# tides_v40.net
KiCad netlist of a schematic drawn in EAGLE
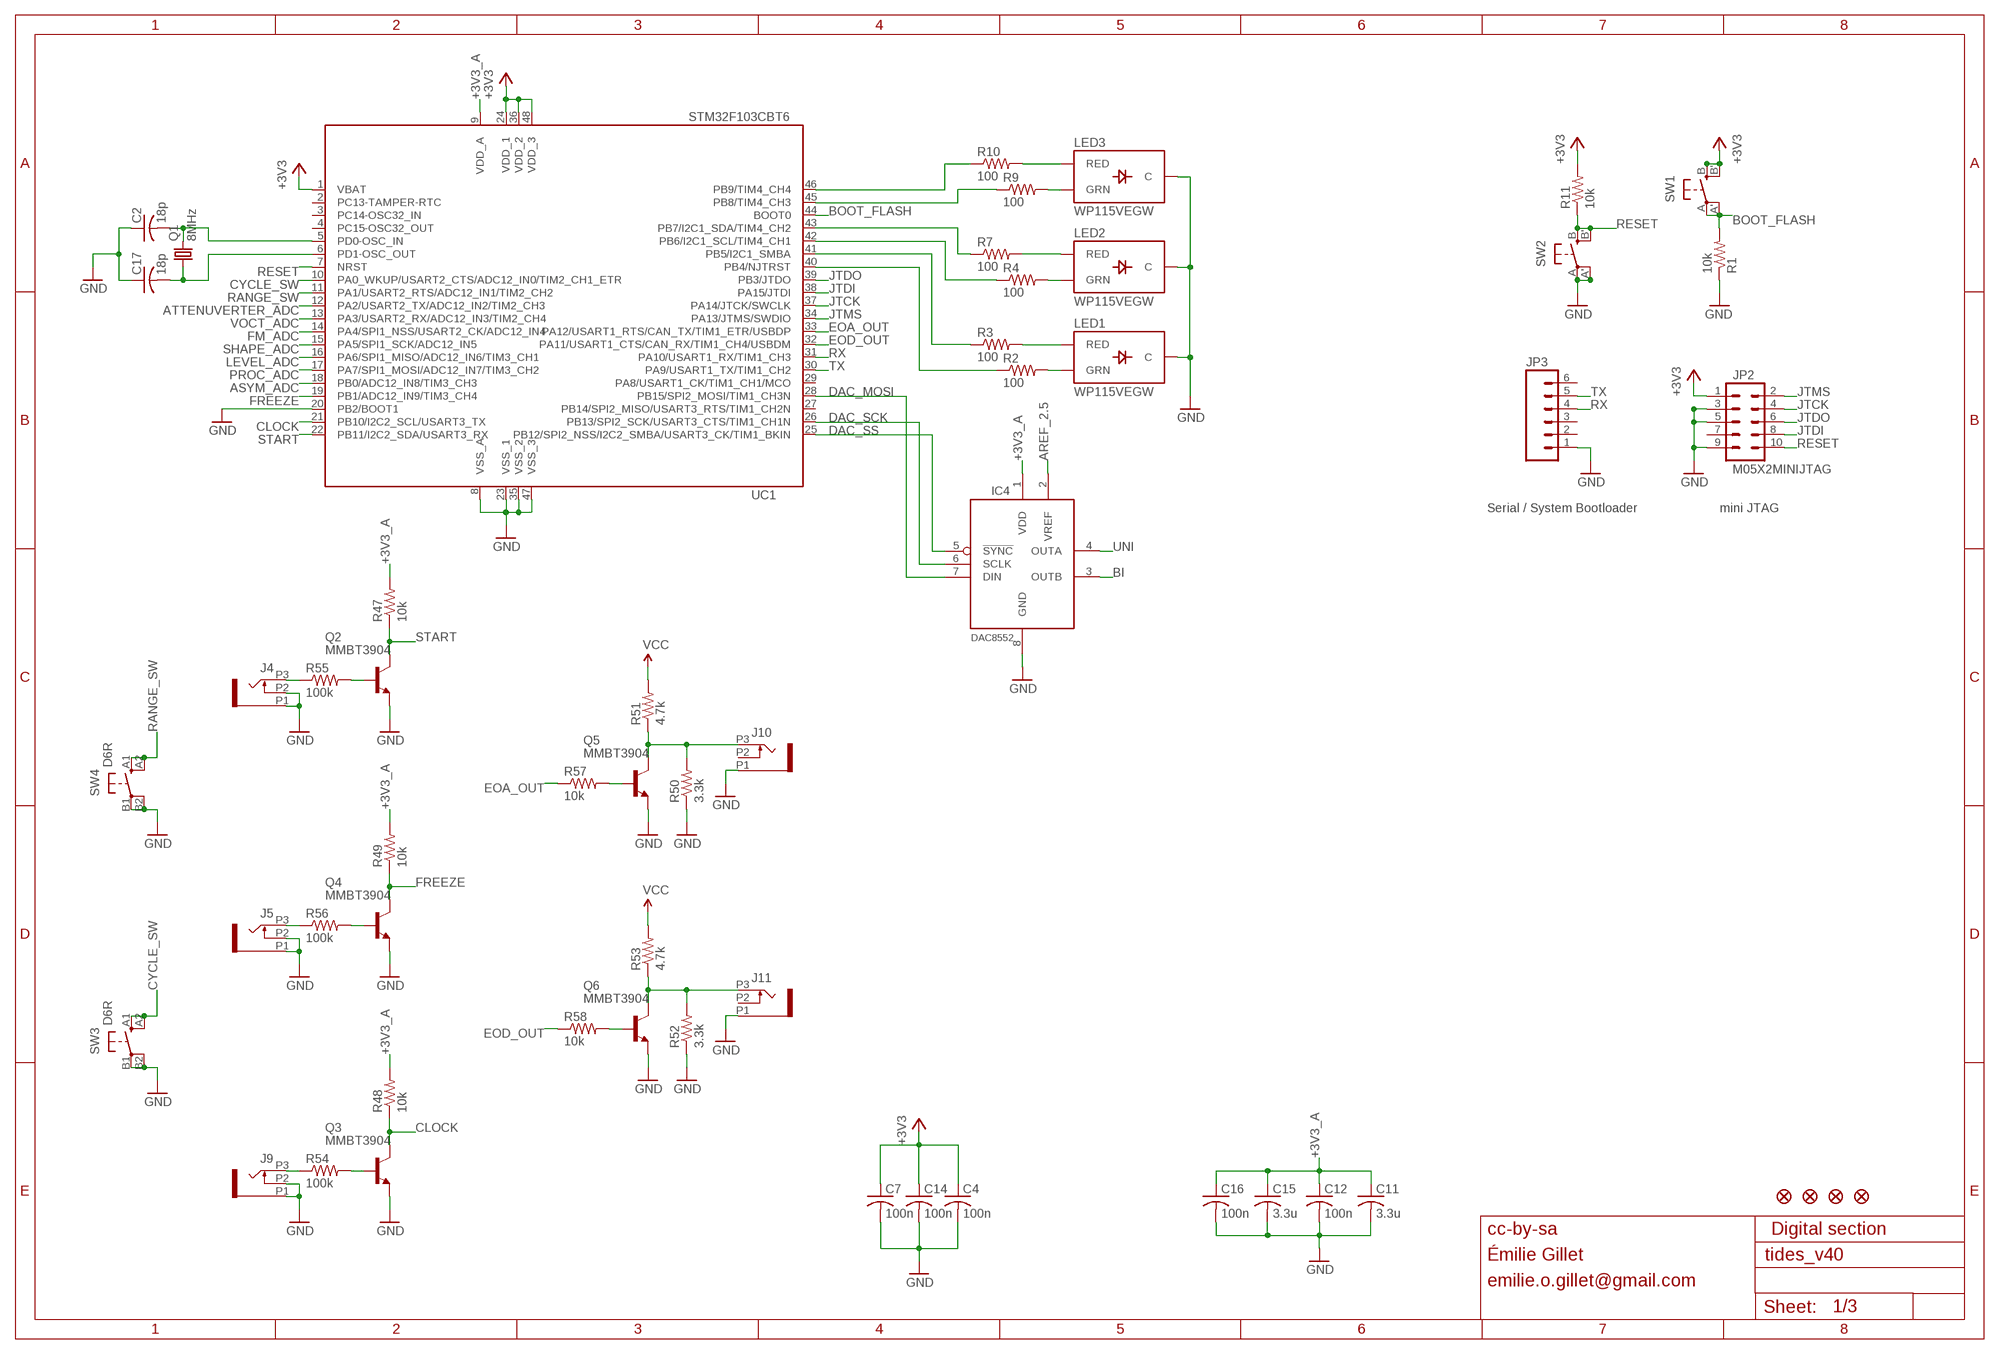
[diagram p0: schematic, sheet 1]
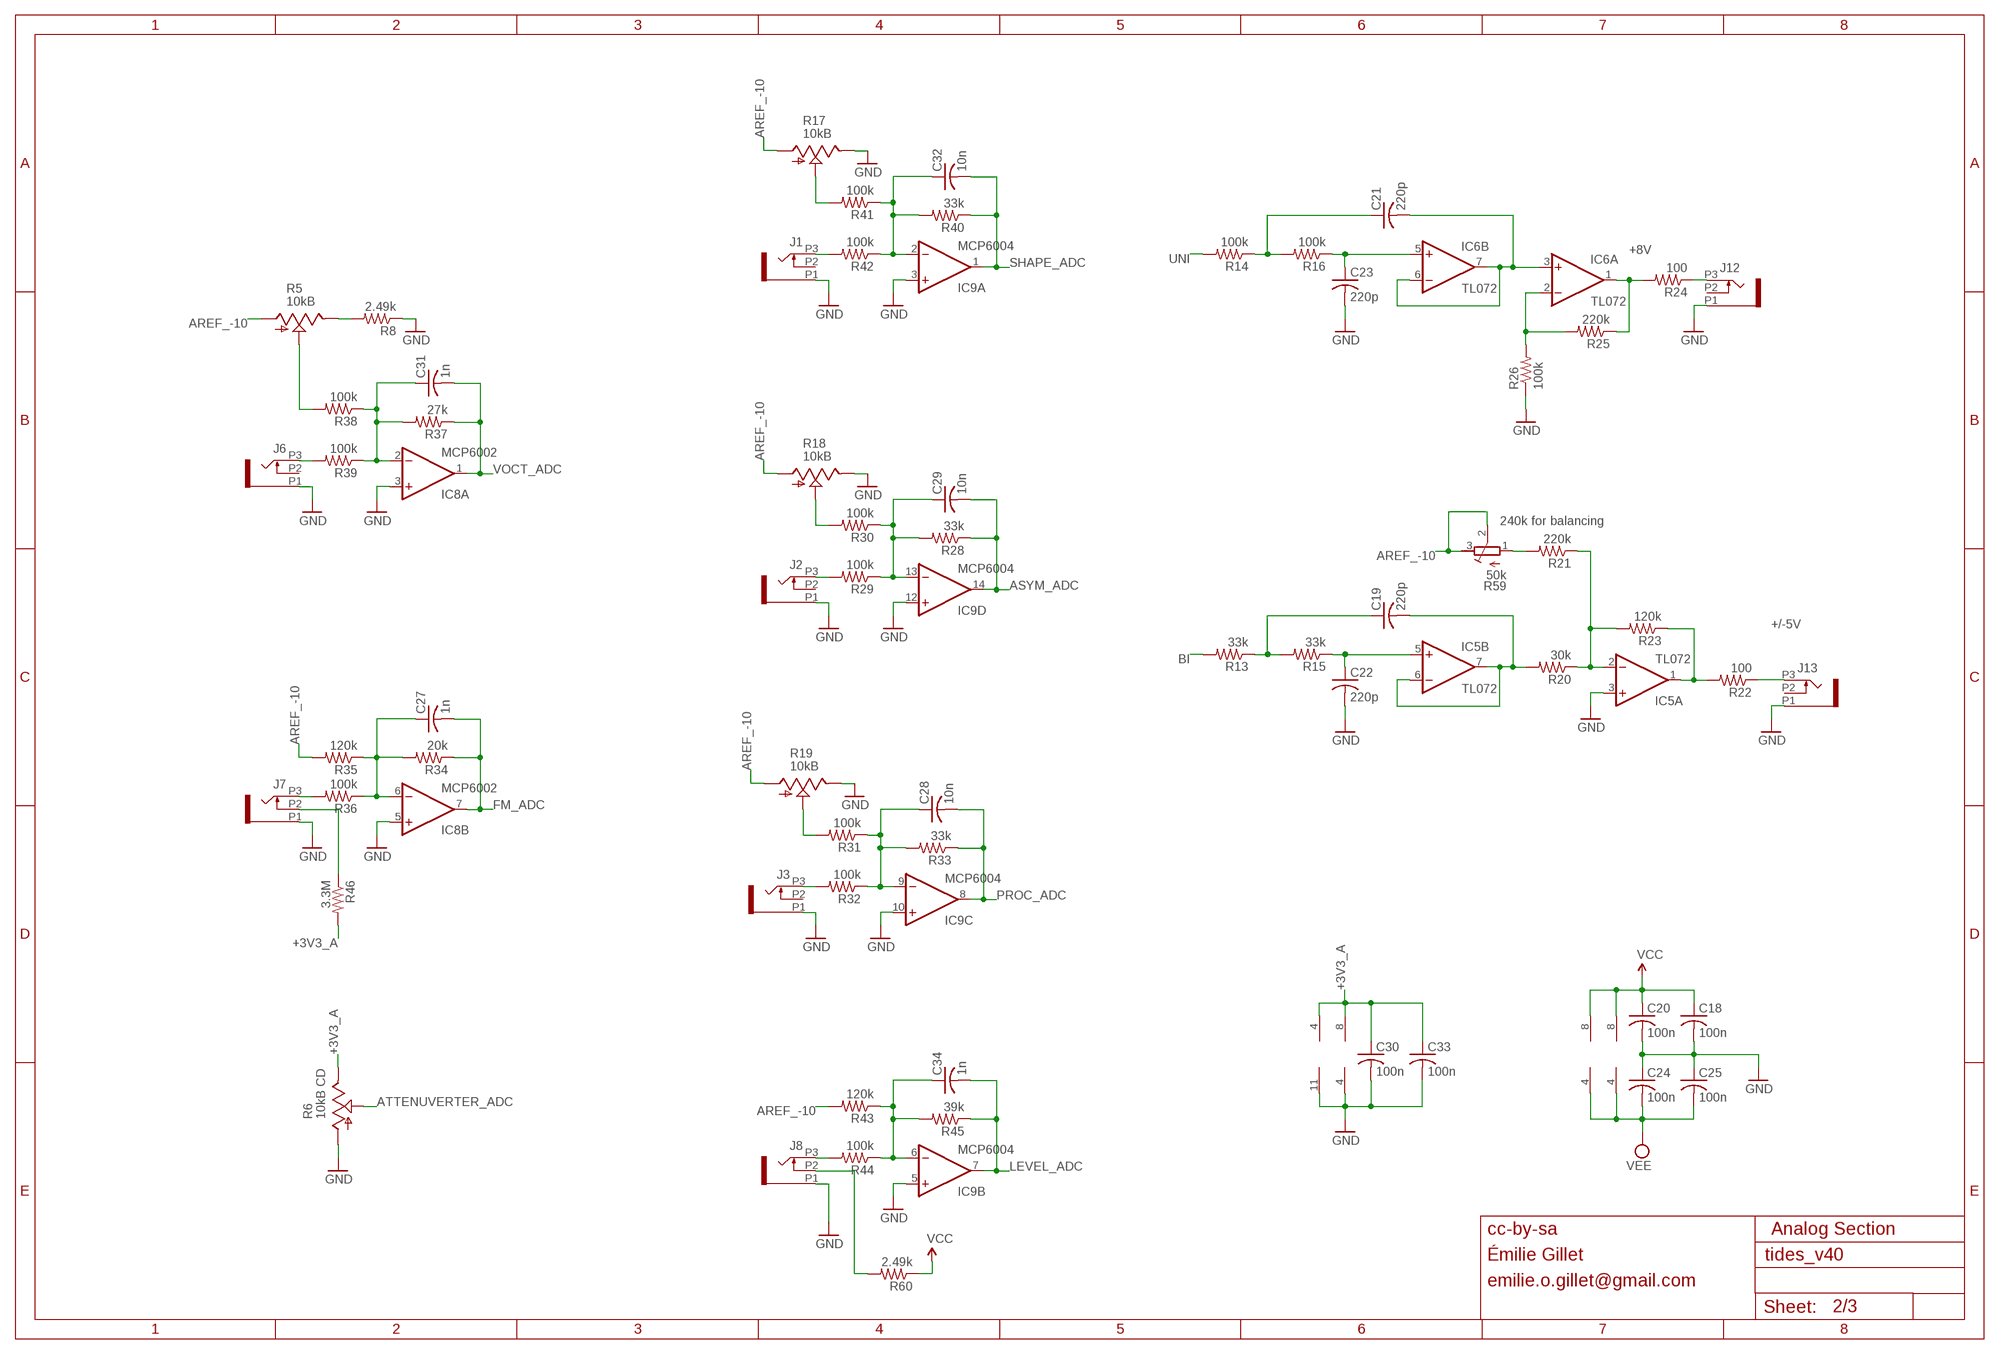
[diagram p1: schematic, sheet 2]
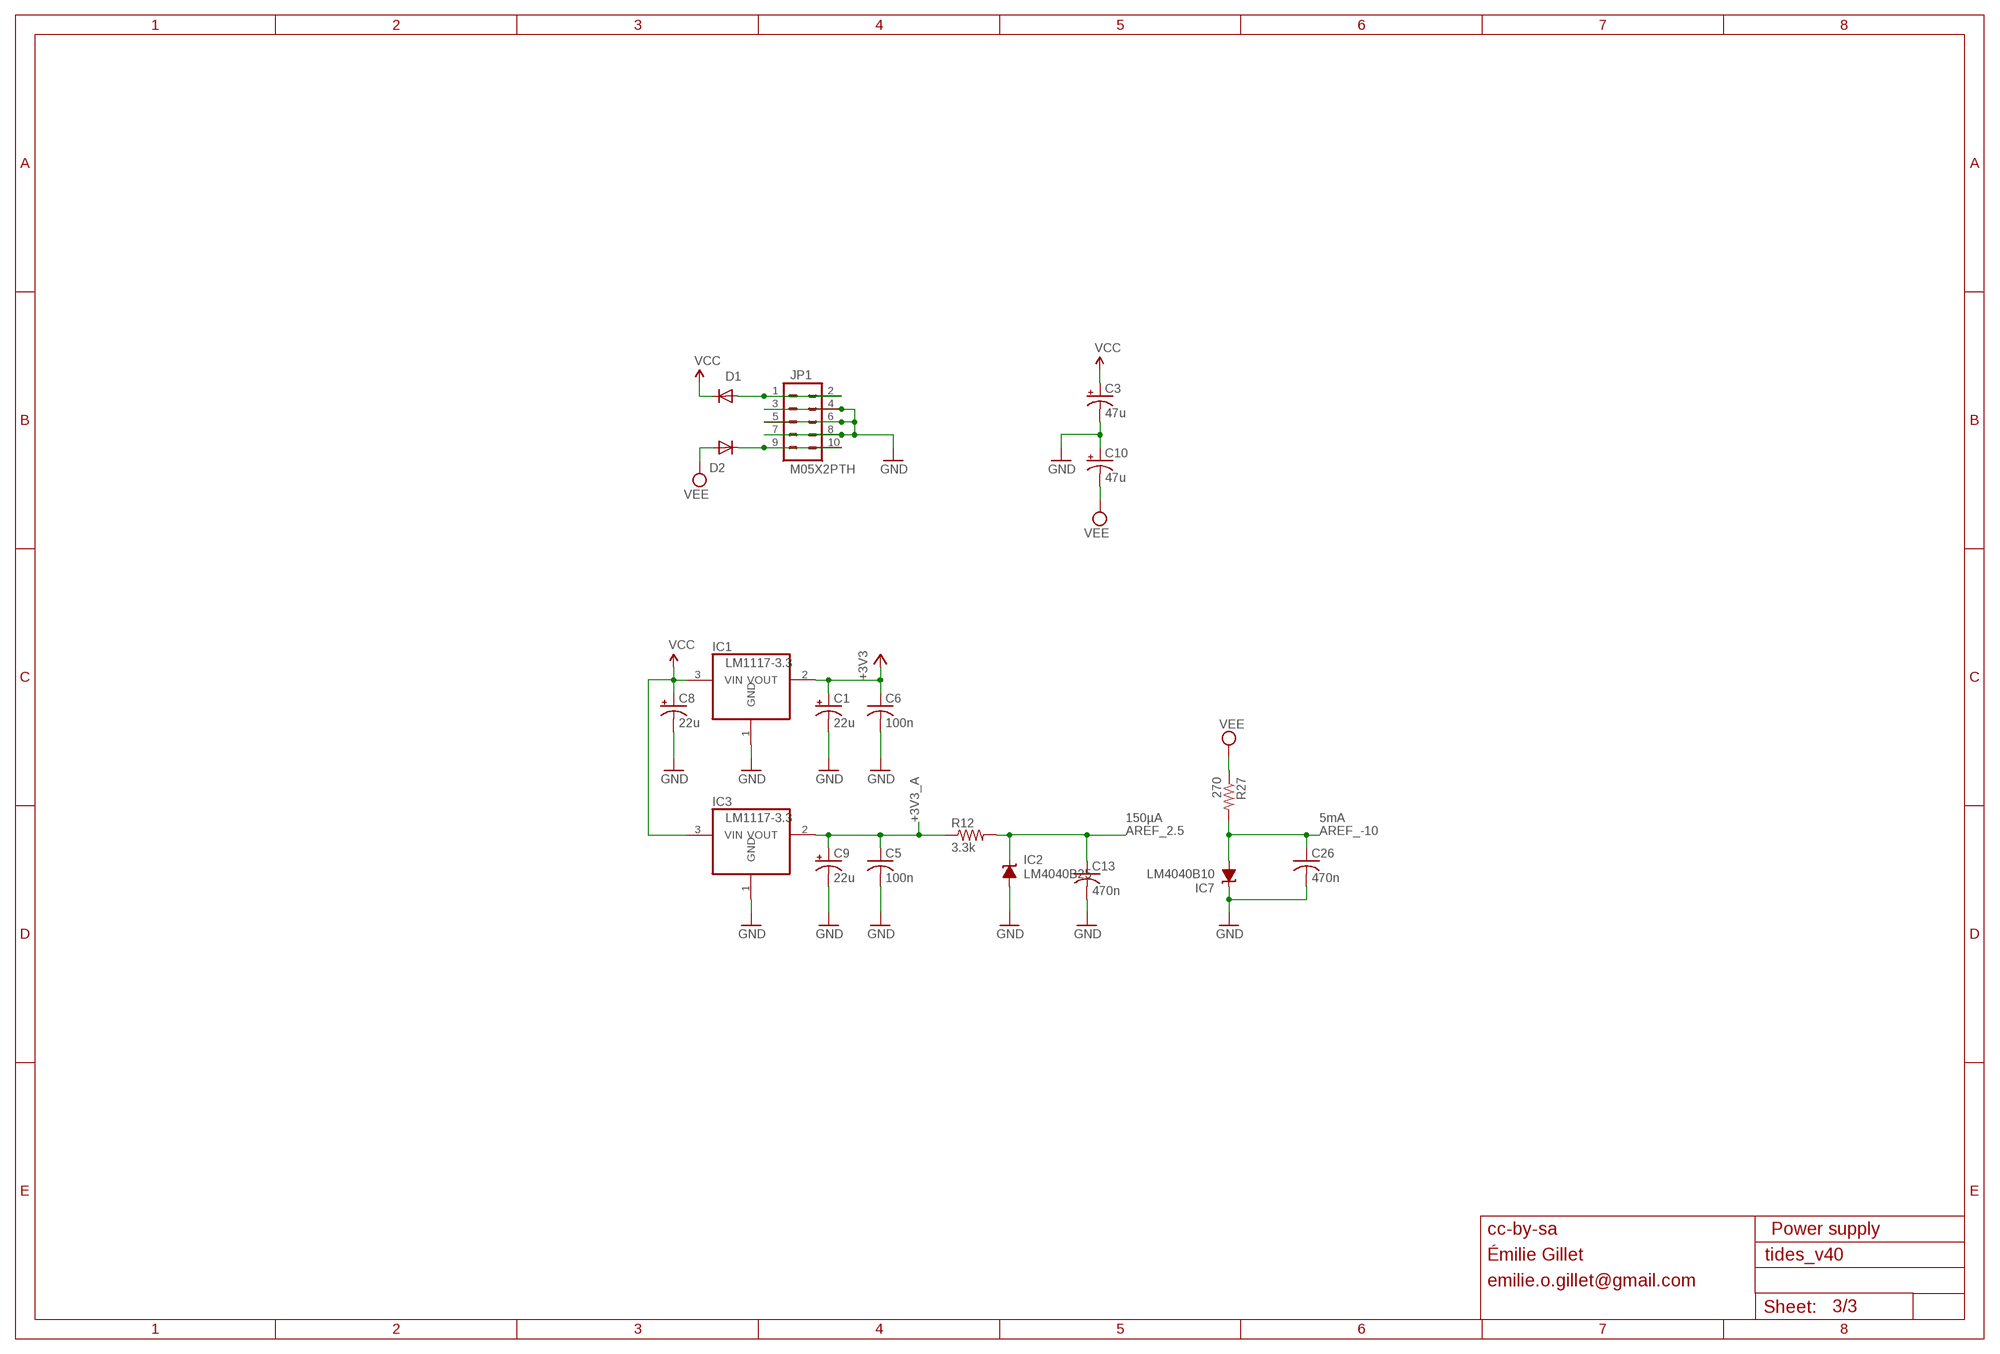
[diagram p2: schematic, sheet 3]

(export (version "E")
  (design (tool "Eeschema 10.0.6"))
  (components
    (comp (ref "C2")
      (value "18p")
      (footprint "eagle-import:C0603")
      (libsource (lib "eagle-import") (part "C-USC0603"))
    )
    (comp (ref "C4")
      (value "100n")
      (footprint "eagle-import:C0603")
      (libsource (lib "eagle-import") (part "C-USC0603"))
    )
    (comp (ref "C7")
      (value "100n")
      (footprint "eagle-import:C0603")
      (libsource (lib "eagle-import") (part "C-USC0603"))
    )
    (comp (ref "C11")
      (value "3.3u")
      (footprint "eagle-import:C0603")
      (libsource (lib "eagle-import") (part "C-USC0603"))
    )
    (comp (ref "C12")
      (value "100n")
      (footprint "eagle-import:C0603")
      (libsource (lib "eagle-import") (part "C-USC0603"))
    )
    (comp (ref "C14")
      (value "100n")
      (footprint "eagle-import:C0603")
      (libsource (lib "eagle-import") (part "C-USC0603"))
    )
    (comp (ref "C15")
      (value "3.3u")
      (footprint "eagle-import:C0603")
      (libsource (lib "eagle-import") (part "C-USC0603"))
    )
    (comp (ref "C16")
      (value "100n")
      (footprint "eagle-import:C0603")
      (libsource (lib "eagle-import") (part "C-USC0603"))
    )
    (comp (ref "C17")
      (value "18p")
      (footprint "eagle-import:C0603")
      (libsource (lib "eagle-import") (part "C-USC0603"))
    )
    (comp (ref "IC4")
      (value "DAC8552")
      (footprint "eagle-import:MSOP-8")
      (libsource (lib "eagle-import") (part "DAC8552"))
    )
    (comp (ref "J4")
      (value "PJ301_THONKICONN6")
      (footprint "eagle-import:WQP_PJ_301M6")
      (libsource (lib "eagle-import") (part "PJ301_THONKICONN6"))
    )
    (comp (ref "J5")
      (value "PJ301_THONKICONN6")
      (footprint "eagle-import:WQP_PJ_301M6")
      (libsource (lib "eagle-import") (part "PJ301_THONKICONN6"))
    )
    (comp (ref "J9")
      (value "PJ301_THONKICONN6")
      (footprint "eagle-import:WQP_PJ_301M6")
      (libsource (lib "eagle-import") (part "PJ301_THONKICONN6"))
    )
    (comp (ref "J10")
      (value "PJ301_THONKICONN6")
      (footprint "eagle-import:WQP_PJ_301M6")
      (libsource (lib "eagle-import") (part "PJ301_THONKICONN6"))
    )
    (comp (ref "J11")
      (value "PJ301_THONKICONN6")
      (footprint "eagle-import:WQP_PJ_301M6")
      (libsource (lib "eagle-import") (part "PJ301_THONKICONN6"))
    )
    (comp (ref "JP2")
      (value "M05X2MINIJTAG")
      (footprint "eagle-import:2X5-1.27")
      (libsource (lib "eagle-import") (part "M05X2MINIJTAG"))
    )
    (comp (ref "JP3")
      (value "M06SIP")
      (footprint "eagle-import:1X06")
      (libsource (lib "eagle-import") (part "M06SIP"))
    )
    (comp (ref "JP4")
      (value "FIDUCIAL1X2")
      (footprint "eagle-import:FIDUCIAL-1X2")
      (libsource (lib "eagle-import") (part "FIDUCIAL1X2"))
    )
    (comp (ref "JP5")
      (value "FIDUCIAL1X2")
      (footprint "eagle-import:FIDUCIAL-1X2")
      (libsource (lib "eagle-import") (part "FIDUCIAL1X2"))
    )
    (comp (ref "JP6")
      (value "FIDUCIAL1X2")
      (footprint "eagle-import:FIDUCIAL-1X2")
      (libsource (lib "eagle-import") (part "FIDUCIAL1X2"))
    )
    (comp (ref "JP7")
      (value "FIDUCIAL1X2")
      (footprint "eagle-import:FIDUCIAL-1X2")
      (libsource (lib "eagle-import") (part "FIDUCIAL1X2"))
    )
    (comp (ref "LED1")
      (value "WP115VEGW")
      (footprint "eagle-import:LED-BICOLOR-THROUGHHOLE")
      (libsource (lib "eagle-import") (part "LED-BICOLOR-THROUGHHOLE"))
    )
    (comp (ref "LED2")
      (value "WP115VEGW")
      (footprint "eagle-import:LED-BICOLOR-THROUGHHOLE")
      (libsource (lib "eagle-import") (part "LED-BICOLOR-THROUGHHOLE"))
    )
    (comp (ref "LED3")
      (value "WP115VEGW")
      (footprint "eagle-import:LED-BICOLOR-THROUGHHOLE")
      (libsource (lib "eagle-import") (part "LED-BICOLOR-THROUGHHOLE"))
    )
    (comp (ref "Q1")
      (value "8MHz")
      (footprint "eagle-import:HC49UP")
      (libsource (lib "eagle-import") (part "CRYSTALHC49UP"))
    )
    (comp (ref "Q2")
      (value "MMBT3904")
      (footprint "eagle-import:SOT23-BEC")
      (libsource (lib "eagle-import") (part "-NPN-SOT23-BECMMBT3904LT1"))
    )
    (comp (ref "Q3")
      (value "MMBT3904")
      (footprint "eagle-import:SOT23-BEC")
      (libsource (lib "eagle-import") (part "-NPN-SOT23-BECMMBT3904LT1"))
    )
    (comp (ref "Q4")
      (value "MMBT3904")
      (footprint "eagle-import:SOT23-BEC")
      (libsource (lib "eagle-import") (part "-NPN-SOT23-BECMMBT3904LT1"))
    )
    (comp (ref "Q5")
      (value "MMBT3904")
      (footprint "eagle-import:SOT23-BEC")
      (libsource (lib "eagle-import") (part "-NPN-SOT23-BECMMBT3904LT1"))
    )
    (comp (ref "Q6")
      (value "MMBT3904")
      (footprint "eagle-import:SOT23-BEC")
      (libsource (lib "eagle-import") (part "-NPN-SOT23-BECMMBT3904LT1"))
    )
    (comp (ref "R1")
      (value "10k")
      (footprint "eagle-import:R0603")
      (libsource (lib "eagle-import") (part "R-US_R0603"))
    )
    (comp (ref "R2")
      (value "100")
      (footprint "eagle-import:R0603")
      (libsource (lib "eagle-import") (part "R-US_R0603"))
    )
    (comp (ref "R3")
      (value "100")
      (footprint "eagle-import:R0603")
      (libsource (lib "eagle-import") (part "R-US_R0603"))
    )
    (comp (ref "R4")
      (value "100")
      (footprint "eagle-import:R0603")
      (libsource (lib "eagle-import") (part "R-US_R0603"))
    )
    (comp (ref "R7")
      (value "100")
      (footprint "eagle-import:R0603")
      (libsource (lib "eagle-import") (part "R-US_R0603"))
    )
    (comp (ref "R9")
      (value "100")
      (footprint "eagle-import:R0603")
      (libsource (lib "eagle-import") (part "R-US_R0603"))
    )
    (comp (ref "R10")
      (value "100")
      (footprint "eagle-import:R0603")
      (libsource (lib "eagle-import") (part "R-US_R0603"))
    )
    (comp (ref "R11")
      (value "10k")
      (footprint "eagle-import:R0603")
      (libsource (lib "eagle-import") (part "R-US_R0603"))
    )
    (comp (ref "R47")
      (value "10k")
      (footprint "eagle-import:R0603")
      (libsource (lib "eagle-import") (part "R-US_R0603"))
    )
    (comp (ref "R48")
      (value "10k")
      (footprint "eagle-import:R0603")
      (libsource (lib "eagle-import") (part "R-US_R0603"))
    )
    (comp (ref "R49")
      (value "10k")
      (footprint "eagle-import:R0603")
      (libsource (lib "eagle-import") (part "R-US_R0603"))
    )
    (comp (ref "R50")
      (value "3.3k")
      (footprint "eagle-import:R0603")
      (libsource (lib "eagle-import") (part "R-US_R0603"))
    )
    (comp (ref "R51")
      (value "4.7k")
      (footprint "eagle-import:R0603")
      (libsource (lib "eagle-import") (part "R-US_R0603"))
    )
    (comp (ref "R52")
      (value "3.3k")
      (footprint "eagle-import:R0603")
      (libsource (lib "eagle-import") (part "R-US_R0603"))
    )
    (comp (ref "R53")
      (value "4.7k")
      (footprint "eagle-import:R0603")
      (libsource (lib "eagle-import") (part "R-US_R0603"))
    )
    (comp (ref "R54")
      (value "100k")
      (footprint "eagle-import:R0603")
      (libsource (lib "eagle-import") (part "R-US_R0603"))
    )
    (comp (ref "R55")
      (value "100k")
      (footprint "eagle-import:R0603")
      (libsource (lib "eagle-import") (part "R-US_R0603"))
    )
    (comp (ref "R56")
      (value "100k")
      (footprint "eagle-import:R0603")
      (libsource (lib "eagle-import") (part "R-US_R0603"))
    )
    (comp (ref "R57")
      (value "10k")
      (footprint "eagle-import:R0603")
      (libsource (lib "eagle-import") (part "R-US_R0603"))
    )
    (comp (ref "R58")
      (value "10k")
      (footprint "eagle-import:R0603")
      (libsource (lib "eagle-import") (part "R-US_R0603"))
    )
    (comp (ref "SW1")
      (value "EVQQ2")
      (footprint "eagle-import:EVQ-Q2")
      (libsource (lib "eagle-import") (part "EVQQ2"))
    )
    (comp (ref "SW2")
      (value "EVQQ2")
      (footprint "eagle-import:EVQ-Q2")
      (libsource (lib "eagle-import") (part "EVQQ2"))
    )
    (comp (ref "SW3")
      (value "D6R")
      (footprint "eagle-import:D6R")
      (libsource (lib "eagle-import") (part "D6R"))
    )
    (comp (ref "SW4")
      (value "D6R")
      (footprint "eagle-import:D6R")
      (libsource (lib "eagle-import") (part "D6R"))
    )
    (comp (ref "UC1")
      (value "STM32F103CBT6")
      (footprint "eagle-import:LQFP48")
      (libsource (lib "eagle-import") (part "STM32F103CB"))
    )
    (comp (ref "C1")
      (value "22u")
      (footprint "eagle-import:PANASONIC_C")
      (libsource (lib "eagle-import") (part "CPOL-USC"))
    )
    (comp (ref "C3")
      (value "47u")
      (footprint "eagle-import:PANASONIC_D")
      (libsource (lib "eagle-import") (part "CPOL-USD"))
    )
    (comp (ref "C5")
      (value "100n")
      (footprint "eagle-import:C0603")
      (libsource (lib "eagle-import") (part "C-USC0603"))
    )
    (comp (ref "C6")
      (value "100n")
      (footprint "eagle-import:C0603")
      (libsource (lib "eagle-import") (part "C-USC0603"))
    )
    (comp (ref "C8")
      (value "22u")
      (footprint "eagle-import:PANASONIC_C")
      (libsource (lib "eagle-import") (part "CPOL-USC"))
    )
    (comp (ref "C9")
      (value "22u")
      (footprint "eagle-import:PANASONIC_C")
      (libsource (lib "eagle-import") (part "CPOL-USC"))
    )
    (comp (ref "C10")
      (value "47u")
      (footprint "eagle-import:PANASONIC_D")
      (libsource (lib "eagle-import") (part "CPOL-USD"))
    )
    (comp (ref "C13")
      (value "470n")
      (footprint "eagle-import:C0603")
      (libsource (lib "eagle-import") (part "C-USC0603"))
    )
    (comp (ref "C26")
      (value "470n")
      (footprint "eagle-import:C0603")
      (libsource (lib "eagle-import") (part "C-USC0603"))
    )
    (comp (ref "D1")
      (value "1N5819HW")
      (footprint "eagle-import:SOD123")
      (libsource (lib "eagle-import") (part "DIODE-SOD123"))
    )
    (comp (ref "D2")
      (value "1N5819HW")
      (footprint "eagle-import:SOD123")
      (libsource (lib "eagle-import") (part "DIODE-SOD123"))
    )
    (comp (ref "IC1")
      (value "LM1117-3.3")
      (footprint "eagle-import:SOT223")
      (libsource (lib "eagle-import") (part "REG1117"))
    )
    (comp (ref "IC2")
      (value "LM4040B25")
      (footprint "eagle-import:DBZ_R-PDSO-G3")
      (libsource (lib "eagle-import") (part "LM4041DBZB12"))
    )
    (comp (ref "IC3")
      (value "LM1117-3.3")
      (footprint "eagle-import:SOT223")
      (libsource (lib "eagle-import") (part "REG1117"))
    )
    (comp (ref "IC7")
      (value "LM4040B10")
      (footprint "eagle-import:DBZ_R-PDSO-G3")
      (libsource (lib "eagle-import") (part "LM4041DBZB12"))
    )
    (comp (ref "JP1")
      (value "M05X2PTH")
      (footprint "eagle-import:AVR_ICSP")
      (libsource (lib "eagle-import") (part "M05X2PTH"))
    )
    (comp (ref "R12")
      (value "3.3k")
      (footprint "eagle-import:R0603")
      (libsource (lib "eagle-import") (part "R-US_R0603"))
    )
    (comp (ref "R27")
      (value "270")
      (footprint "eagle-import:R0603")
      (libsource (lib "eagle-import") (part "R-US_R0603"))
    )
    (comp (ref "C18")
      (value "100n")
      (footprint "eagle-import:C0603")
      (libsource (lib "eagle-import") (part "C-USC0603"))
    )
    (comp (ref "C19")
      (value "220p")
      (footprint "eagle-import:C0603")
      (libsource (lib "eagle-import") (part "C-USC0603"))
    )
    (comp (ref "C20")
      (value "100n")
      (footprint "eagle-import:C0603")
      (libsource (lib "eagle-import") (part "C-USC0603"))
    )
    (comp (ref "C21")
      (value "220p")
      (footprint "eagle-import:C0603")
      (libsource (lib "eagle-import") (part "C-USC0603"))
    )
    (comp (ref "C22")
      (value "220p")
      (footprint "eagle-import:C0603")
      (libsource (lib "eagle-import") (part "C-USC0603"))
    )
    (comp (ref "C23")
      (value "220p")
      (footprint "eagle-import:C0603")
      (libsource (lib "eagle-import") (part "C-USC0603"))
    )
    (comp (ref "C24")
      (value "100n")
      (footprint "eagle-import:C0603")
      (libsource (lib "eagle-import") (part "C-USC0603"))
    )
    (comp (ref "C25")
      (value "100n")
      (footprint "eagle-import:C0603")
      (libsource (lib "eagle-import") (part "C-USC0603"))
    )
    (comp (ref "C27")
      (value "1n")
      (footprint "eagle-import:C0603")
      (libsource (lib "eagle-import") (part "C-USC0603"))
    )
    (comp (ref "C28")
      (value "10n")
      (footprint "eagle-import:C0603")
      (libsource (lib "eagle-import") (part "C-USC0603"))
    )
    (comp (ref "C29")
      (value "10n")
      (footprint "eagle-import:C0603")
      (libsource (lib "eagle-import") (part "C-USC0603"))
    )
    (comp (ref "C30")
      (value "100n")
      (footprint "eagle-import:C0603")
      (libsource (lib "eagle-import") (part "C-USC0603"))
    )
    (comp (ref "C31")
      (value "1n")
      (footprint "eagle-import:C0603")
      (libsource (lib "eagle-import") (part "C-USC0603"))
    )
    (comp (ref "C32")
      (value "10n")
      (footprint "eagle-import:C0603")
      (libsource (lib "eagle-import") (part "C-USC0603"))
    )
    (comp (ref "C33")
      (value "100n")
      (footprint "eagle-import:C0603")
      (libsource (lib "eagle-import") (part "C-USC0603"))
    )
    (comp (ref "C34")
      (value "1n")
      (footprint "eagle-import:C0603")
      (libsource (lib "eagle-import") (part "C-USC0603"))
    )
    (comp (ref "IC5")
      (value "TL072")
      (footprint "eagle-import:SO08")
      (libsource (lib "eagle-import") (part "TL072D"))
    )
    (comp (ref "IC6")
      (value "TL072")
      (footprint "eagle-import:SO08")
      (libsource (lib "eagle-import") (part "TL072D"))
    )
    (comp (ref "IC8")
      (value "MCP6002")
      (footprint "eagle-import:SO08")
      (libsource (lib "eagle-import") (part "TL072D"))
    )
    (comp (ref "IC9")
      (value "MCP6004")
      (footprint "eagle-import:SO14")
      (libsource (lib "eagle-import") (part "TL074D"))
    )
    (comp (ref "J1")
      (value "PJ301_THONKICONN6")
      (footprint "eagle-import:WQP_PJ_301M6")
      (libsource (lib "eagle-import") (part "PJ301_THONKICONN6"))
    )
    (comp (ref "J2")
      (value "PJ301_THONKICONN6")
      (footprint "eagle-import:WQP_PJ_301M6")
      (libsource (lib "eagle-import") (part "PJ301_THONKICONN6"))
    )
    (comp (ref "J3")
      (value "PJ301_THONKICONN6")
      (footprint "eagle-import:WQP_PJ_301M6")
      (libsource (lib "eagle-import") (part "PJ301_THONKICONN6"))
    )
    (comp (ref "J6")
      (value "PJ301_THONKICONN6")
      (footprint "eagle-import:WQP_PJ_301M6")
      (libsource (lib "eagle-import") (part "PJ301_THONKICONN6"))
    )
    (comp (ref "J7")
      (value "PJ301_THONKICONN6")
      (footprint "eagle-import:WQP_PJ_301M6")
      (libsource (lib "eagle-import") (part "PJ301_THONKICONN6"))
    )
    (comp (ref "J8")
      (value "PJ301_THONKICONN6")
      (footprint "eagle-import:WQP_PJ_301M6")
      (libsource (lib "eagle-import") (part "PJ301_THONKICONN6"))
    )
    (comp (ref "J12")
      (value "PJ301_THONKICONN6")
      (footprint "eagle-import:WQP_PJ_301M6")
      (libsource (lib "eagle-import") (part "PJ301_THONKICONN6"))
    )
    (comp (ref "J13")
      (value "PJ301_THONKICONN6")
      (footprint "eagle-import:WQP_PJ_301M6")
      (libsource (lib "eagle-import") (part "PJ301_THONKICONN6"))
    )
    (comp (ref "R5")
      (value "10kB")
      (footprint "eagle-import:ALPS_POT_VERTICAL_PS")
      (libsource (lib "eagle-import") (part "POT_USVERTICAL_PS"))
    )
    (comp (ref "R6")
      (value "10kB CD")
      (footprint "eagle-import:ALPS_POT_VERTICAL_PS")
      (libsource (lib "eagle-import") (part "POT_USVERTICAL_PS"))
    )
    (comp (ref "R8")
      (value "2.49k")
      (footprint "eagle-import:R0603")
      (libsource (lib "eagle-import") (part "R-US_R0603"))
    )
    (comp (ref "R13")
      (value "33k")
      (footprint "eagle-import:R0603")
      (libsource (lib "eagle-import") (part "R-US_R0603"))
    )
    (comp (ref "R14")
      (value "100k")
      (footprint "eagle-import:R0603")
      (libsource (lib "eagle-import") (part "R-US_R0603"))
    )
    (comp (ref "R15")
      (value "33k")
      (footprint "eagle-import:R0603")
      (libsource (lib "eagle-import") (part "R-US_R0603"))
    )
    (comp (ref "R16")
      (value "100k")
      (footprint "eagle-import:R0603")
      (libsource (lib "eagle-import") (part "R-US_R0603"))
    )
    (comp (ref "R17")
      (value "10kB")
      (footprint "eagle-import:ALPS_POT_VERTICAL_PS")
      (libsource (lib "eagle-import") (part "POT_USVERTICAL_PS"))
    )
    (comp (ref "R18")
      (value "10kB")
      (footprint "eagle-import:ALPS_POT_VERTICAL_PS")
      (libsource (lib "eagle-import") (part "POT_USVERTICAL_PS"))
    )
    (comp (ref "R19")
      (value "10kB")
      (footprint "eagle-import:ALPS_POT_VERTICAL_PS")
      (libsource (lib "eagle-import") (part "POT_USVERTICAL_PS"))
    )
    (comp (ref "R20")
      (value "30k")
      (footprint "eagle-import:R0603")
      (libsource (lib "eagle-import") (part "R-US_R0603"))
    )
    (comp (ref "R21")
      (value "220k")
      (footprint "eagle-import:R0603")
      (libsource (lib "eagle-import") (part "R-US_R0603"))
    )
    (comp (ref "R22")
      (value "100")
      (footprint "eagle-import:R0603")
      (libsource (lib "eagle-import") (part "R-US_R0603"))
    )
    (comp (ref "R23")
      (value "120k")
      (footprint "eagle-import:R0603")
      (libsource (lib "eagle-import") (part "R-US_R0603"))
    )
    (comp (ref "R24")
      (value "100")
      (footprint "eagle-import:R0603")
      (libsource (lib "eagle-import") (part "R-US_R0603"))
    )
    (comp (ref "R25")
      (value "220k")
      (footprint "eagle-import:R0603")
      (libsource (lib "eagle-import") (part "R-US_R0603"))
    )
    (comp (ref "R26")
      (value "100k")
      (footprint "eagle-import:R0603")
      (libsource (lib "eagle-import") (part "R-US_R0603"))
    )
    (comp (ref "R28")
      (value "33k")
      (footprint "eagle-import:R0603")
      (libsource (lib "eagle-import") (part "R-US_R0603"))
    )
    (comp (ref "R29")
      (value "100k")
      (footprint "eagle-import:R0603")
      (libsource (lib "eagle-import") (part "R-US_R0603"))
    )
    (comp (ref "R30")
      (value "100k")
      (footprint "eagle-import:R0603")
      (libsource (lib "eagle-import") (part "R-US_R0603"))
    )
    (comp (ref "R31")
      (value "100k")
      (footprint "eagle-import:R0603")
      (libsource (lib "eagle-import") (part "R-US_R0603"))
    )
    (comp (ref "R32")
      (value "100k")
      (footprint "eagle-import:R0603")
      (libsource (lib "eagle-import") (part "R-US_R0603"))
    )
    (comp (ref "R33")
      (value "33k")
      (footprint "eagle-import:R0603")
      (libsource (lib "eagle-import") (part "R-US_R0603"))
    )
    (comp (ref "R34")
      (value "20k")
      (footprint "eagle-import:R0603")
      (libsource (lib "eagle-import") (part "R-US_R0603"))
    )
    (comp (ref "R35")
      (value "120k")
      (footprint "eagle-import:R0603")
      (libsource (lib "eagle-import") (part "R-US_R0603"))
    )
    (comp (ref "R36")
      (value "100k")
      (footprint "eagle-import:R0603")
      (libsource (lib "eagle-import") (part "R-US_R0603"))
    )
    (comp (ref "R37")
      (value "27k")
      (footprint "eagle-import:R0603")
      (libsource (lib "eagle-import") (part "R-US_R0603"))
    )
    (comp (ref "R38")
      (value "100k")
      (footprint "eagle-import:R0603")
      (libsource (lib "eagle-import") (part "R-US_R0603"))
    )
    (comp (ref "R39")
      (value "100k")
      (footprint "eagle-import:R0603")
      (libsource (lib "eagle-import") (part "R-US_R0603"))
    )
    (comp (ref "R40")
      (value "33k")
      (footprint "eagle-import:R0603")
      (libsource (lib "eagle-import") (part "R-US_R0603"))
    )
    (comp (ref "R41")
      (value "100k")
      (footprint "eagle-import:R0603")
      (libsource (lib "eagle-import") (part "R-US_R0603"))
    )
    (comp (ref "R42")
      (value "100k")
      (footprint "eagle-import:R0603")
      (libsource (lib "eagle-import") (part "R-US_R0603"))
    )
    (comp (ref "R43")
      (value "120k")
      (footprint "eagle-import:R0603")
      (libsource (lib "eagle-import") (part "R-US_R0603"))
    )
    (comp (ref "R44")
      (value "100k")
      (footprint "eagle-import:R0603")
      (libsource (lib "eagle-import") (part "R-US_R0603"))
    )
    (comp (ref "R45")
      (value "39k")
      (footprint "eagle-import:R0603")
      (libsource (lib "eagle-import") (part "R-US_R0603"))
    )
    (comp (ref "R46")
      (value "3.3M")
      (footprint "eagle-import:R0603")
      (libsource (lib "eagle-import") (part "R-US_R0603"))
    )
    (comp (ref "R59")
      (value "50k")
      (footprint "eagle-import:RTRIM3296X")
      (libsource (lib "eagle-import") (part "R-TRIMM3296X"))
    )
    (comp (ref "R60")
      (value "2.49k")
      (footprint "eagle-import:R0805")
      (libsource (lib "eagle-import") (part "R-US_R0805"))
    )
  )
  (nets
    (net (code "1") (name "+3V3") (class "Default")
      (node (ref "C1") (pin "+") (pinfunction "+_+") (pintype "passive"))
      (node (ref "C14") (pin "1") (pinfunction "1_1") (pintype "passive"))
      (node (ref "C4") (pin "1") (pinfunction "1_1") (pintype "passive"))
      (node (ref "C6") (pin "1") (pinfunction "1_1") (pintype "passive"))
      (node (ref "C7") (pin "1") (pinfunction "1_1") (pintype "passive"))
      (node (ref "IC1") (pin "2") (pinfunction "VOUT_2") (pintype "output"))
      (node (ref "JP2") (pin "1") (pinfunction "1_1") (pintype "passive"))
      (node (ref "R11") (pin "2") (pinfunction "2_2") (pintype "passive"))
      (node (ref "SW1") (pin "B") (pinfunction "S_B") (pintype "passive"))
      (node (ref "SW1") (pin "B'") (pinfunction "S1_B'") (pintype "passive"))
      (node (ref "UC1") (pin "1") (pinfunction "VBAT_1") (pintype "power_in"))
      (node (ref "UC1") (pin "24") (pinfunction "VDD_1_24") (pintype "power_in"))
      (node (ref "UC1") (pin "36") (pinfunction "VDD_2_36") (pintype "power_in"))
      (node (ref "UC1") (pin "48") (pinfunction "VDD_3_48") (pintype "power_in"))
    )
    (net (code "2") (name "+3V3_A") (class "Default")
      (node (ref "C11") (pin "1") (pinfunction "1_1") (pintype "passive"))
      (node (ref "C12") (pin "1") (pinfunction "1_1") (pintype "passive"))
      (node (ref "C15") (pin "1") (pinfunction "1_1") (pintype "passive"))
      (node (ref "C16") (pin "1") (pinfunction "1_1") (pintype "passive"))
      (node (ref "C30") (pin "1") (pinfunction "1_1") (pintype "passive"))
      (node (ref "C33") (pin "1") (pinfunction "1_1") (pintype "passive"))
      (node (ref "C5") (pin "1") (pinfunction "1_1") (pintype "passive"))
      (node (ref "C9") (pin "+") (pinfunction "+_+") (pintype "passive"))
      (node (ref "IC3") (pin "2") (pinfunction "VOUT_2") (pintype "output"))
      (node (ref "IC4") (pin "1") (pinfunction "VDD_1") (pintype "power_in"))
      (node (ref "IC8") (pin "8") (pinfunction "V+_8") (pintype "power_in"))
      (node (ref "IC9") (pin "4") (pinfunction "V+_4") (pintype "power_in"))
      (node (ref "R12") (pin "1") (pinfunction "1_1") (pintype "passive"))
      (node (ref "R46") (pin "2") (pinfunction "2_2") (pintype "passive"))
      (node (ref "R47") (pin "2") (pinfunction "2_2") (pintype "passive"))
      (node (ref "R48") (pin "2") (pinfunction "2_2") (pintype "passive"))
      (node (ref "R49") (pin "2") (pinfunction "2_2") (pintype "passive"))
      (node (ref "R6") (pin "P$1") (pinfunction "E_P$1") (pintype "passive"))
      (node (ref "UC1") (pin "9") (pinfunction "VDD_A_9") (pintype "power_in"))
    )
    (net (code "3") (name "AREF_-10") (class "Default")
      (node (ref "C26") (pin "1") (pinfunction "1_1") (pintype "passive"))
      (node (ref "IC7") (pin "2") (pinfunction "A_2") (pintype "passive"))
      (node (ref "R17") (pin "P$3") (pinfunction "A_P$3") (pintype "passive"))
      (node (ref "R18") (pin "P$3") (pinfunction "A_P$3") (pintype "passive"))
      (node (ref "R19") (pin "P$3") (pinfunction "A_P$3") (pintype "passive"))
      (node (ref "R27") (pin "2") (pinfunction "2_2") (pintype "passive"))
      (node (ref "R35") (pin "2") (pinfunction "2_2") (pintype "passive"))
      (node (ref "R43") (pin "2") (pinfunction "2_2") (pintype "passive"))
      (node (ref "R5") (pin "P$3") (pinfunction "A_P$3") (pintype "passive"))
      (node (ref "R59") (pin "2") (pinfunction "S_2") (pintype "passive"))
      (node (ref "R59") (pin "3") (pinfunction "A_3") (pintype "passive"))
    )
    (net (code "4") (name "AREF_2.5") (class "Default")
      (node (ref "C13") (pin "1") (pinfunction "1_1") (pintype "passive"))
      (node (ref "IC2") (pin "1") (pinfunction "C_1") (pintype "passive"))
      (node (ref "IC4") (pin "2") (pinfunction "VREF_2") (pintype "power_in"))
      (node (ref "R12") (pin "2") (pinfunction "2_2") (pintype "passive"))
    )
    (net (code "5") (name "ASYM_ADC") (class "Default")
      (node (ref "C29") (pin "2") (pinfunction "2_2") (pintype "passive"))
      (node (ref "IC9") (pin "14") (pinfunction "OUT_14") (pintype "output"))
      (node (ref "R28") (pin "1") (pinfunction "1_1") (pintype "passive"))
      (node (ref "UC1") (pin "18") (pinfunction "PB0/ADC12_IN8/TIM3_CH3_18") (pintype "bidirectional"))
    )
    (net (code "6") (name "ATTENUVERTER_ADC") (class "Default")
      (node (ref "R6") (pin "P$2") (pinfunction "S_P$2") (pintype "passive"))
      (node (ref "UC1") (pin "12") (pinfunction "PA2/USART2_TX/ADC12_IN2/TIM2_CH3_12") (pintype "bidirectional"))
    )
    (net (code "7") (name "BI") (class "Default")
      (node (ref "IC4") (pin "3") (pinfunction "OUTB_3") (pintype "input"))
      (node (ref "R13") (pin "2") (pinfunction "2_2") (pintype "passive"))
    )
    (net (code "8") (name "BOOT_FLASH") (class "Default")
      (node (ref "R1") (pin "2") (pinfunction "2_2") (pintype "passive"))
      (node (ref "SW1") (pin "A") (pinfunction "P_A") (pintype "passive"))
      (node (ref "SW1") (pin "A'") (pinfunction "P1_A'") (pintype "passive"))
      (node (ref "UC1") (pin "44") (pinfunction "BOOT0_44") (pintype "input"))
    )
    (net (code "9") (name "CLOCK") (class "Default")
      (node (ref "Q3") (pin "C") (pinfunction "C_C") (pintype "passive"))
      (node (ref "R48") (pin "1") (pinfunction "1_1") (pintype "passive"))
      (node (ref "UC1") (pin "21") (pinfunction "PB10/I2C2_SCL/USART3_TX_21") (pintype "input"))
    )
    (net (code "10") (name "CYCLE_SW") (class "Default")
      (node (ref "SW3") (pin "A1") (pinfunction "S_A1") (pintype "passive"))
      (node (ref "SW3") (pin "A2") (pinfunction "S1_A2") (pintype "passive"))
      (node (ref "UC1") (pin "10") (pinfunction "PA0_WKUP/USART2_CTS/ADC12_IN0/TIM2_CH1_ETR_10") (pintype "bidirectional"))
    )
    (net (code "11") (name "DAC_MOSI") (class "Default")
      (node (ref "IC4") (pin "7") (pinfunction "DIN_7") (pintype "bidirectional"))
      (node (ref "UC1") (pin "28") (pinfunction "PB15/SPI2_MOSI/TIM1_CH3N_28") (pintype "input"))
    )
    (net (code "12") (name "DAC_SCK") (class "Default")
      (node (ref "IC4") (pin "6") (pinfunction "SCLK_6") (pintype "bidirectional"))
      (node (ref "UC1") (pin "26") (pinfunction "PB13/SPI2_SCK/USART3_CTS/TIM1_CH1N_26") (pintype "input"))
    )
    (net (code "13") (name "DAC_SS") (class "Default")
      (node (ref "IC4") (pin "5") (pinfunction "~{SYNC}_5") (pintype "bidirectional"))
      (node (ref "UC1") (pin "25") (pinfunction "PB12/SPI2_NSS/I2C2_SMBA/USART3_CK/TIM1_BKIN_25") (pintype "input"))
    )
    (net (code "14") (name "EOA_OUT") (class "Default")
      (node (ref "R57") (pin "1") (pinfunction "1_1") (pintype "passive"))
      (node (ref "UC1") (pin "33") (pinfunction "PA12/USART1_RTS/CAN_TX/TIM1_ETR/USBDP_33") (pintype "bidirectional"))
    )
    (net (code "15") (name "EOD_OUT") (class "Default")
      (node (ref "R58") (pin "1") (pinfunction "1_1") (pintype "passive"))
      (node (ref "UC1") (pin "32") (pinfunction "PA11/USART1_CTS/CAN_RX/TIM1_CH4/USBDM_32") (pintype "bidirectional"))
    )
    (net (code "16") (name "FM_ADC") (class "Default")
      (node (ref "C27") (pin "2") (pinfunction "2_2") (pintype "passive"))
      (node (ref "IC8") (pin "7") (pinfunction "OUT_7") (pintype "output"))
      (node (ref "R34") (pin "1") (pinfunction "1_1") (pintype "passive"))
      (node (ref "UC1") (pin "14") (pinfunction "PA4/SPI1_NSS/USART2_CK/ADC12_IN4_14") (pintype "bidirectional"))
    )
    (net (code "17") (name "FREEZE") (class "Default")
      (node (ref "Q4") (pin "C") (pinfunction "C_C") (pintype "passive"))
      (node (ref "R49") (pin "1") (pinfunction "1_1") (pintype "passive"))
      (node (ref "UC1") (pin "19") (pinfunction "PB1/ADC12_IN9/TIM3_CH4_19") (pintype "bidirectional"))
    )
    (net (code "18") (name "GND") (class "Default")
      (node (ref "C1") (pin "-") (pinfunction "-_-") (pintype "passive"))
      (node (ref "C10") (pin "+") (pinfunction "+_+") (pintype "passive"))
      (node (ref "C11") (pin "2") (pinfunction "2_2") (pintype "passive"))
      (node (ref "C12") (pin "2") (pinfunction "2_2") (pintype "passive"))
      (node (ref "C13") (pin "2") (pinfunction "2_2") (pintype "passive"))
      (node (ref "C14") (pin "2") (pinfunction "2_2") (pintype "passive"))
      (node (ref "C15") (pin "2") (pinfunction "2_2") (pintype "passive"))
      (node (ref "C16") (pin "2") (pinfunction "2_2") (pintype "passive"))
      (node (ref "C17") (pin "1") (pinfunction "1_1") (pintype "passive"))
      (node (ref "C18") (pin "2") (pinfunction "2_2") (pintype "passive"))
      (node (ref "C2") (pin "1") (pinfunction "1_1") (pintype "passive"))
      (node (ref "C20") (pin "2") (pinfunction "2_2") (pintype "passive"))
      (node (ref "C22") (pin "2") (pinfunction "2_2") (pintype "passive"))
      (node (ref "C23") (pin "2") (pinfunction "2_2") (pintype "passive"))
      (node (ref "C24") (pin "1") (pinfunction "1_1") (pintype "passive"))
      (node (ref "C25") (pin "1") (pinfunction "1_1") (pintype "passive"))
      (node (ref "C26") (pin "2") (pinfunction "2_2") (pintype "passive"))
      (node (ref "C3") (pin "-") (pinfunction "-_-") (pintype "passive"))
      (node (ref "C30") (pin "2") (pinfunction "2_2") (pintype "passive"))
      (node (ref "C33") (pin "2") (pinfunction "2_2") (pintype "passive"))
      (node (ref "C4") (pin "2") (pinfunction "2_2") (pintype "passive"))
      (node (ref "C5") (pin "2") (pinfunction "2_2") (pintype "passive"))
      (node (ref "C6") (pin "2") (pinfunction "2_2") (pintype "passive"))
      (node (ref "C7") (pin "2") (pinfunction "2_2") (pintype "passive"))
      (node (ref "C8") (pin "-") (pinfunction "-_-") (pintype "passive"))
      (node (ref "C9") (pin "-") (pinfunction "-_-") (pintype "passive"))
      (node (ref "IC1") (pin "1") (pinfunction "GND_1") (pintype "power_in"))
      (node (ref "IC2") (pin "2") (pinfunction "A_2") (pintype "passive"))
      (node (ref "IC3") (pin "1") (pinfunction "GND_1") (pintype "power_in"))
      (node (ref "IC4") (pin "8") (pinfunction "GND_8") (pintype "power_in"))
      (node (ref "IC5") (pin "3") (pinfunction "+IN_3") (pintype "input"))
      (node (ref "IC7") (pin "1") (pinfunction "C_1") (pintype "passive"))
      (node (ref "IC8") (pin "3") (pinfunction "+IN_3") (pintype "input"))
      (node (ref "IC8") (pin "4") (pinfunction "V-_4") (pintype "power_in"))
      (node (ref "IC8") (pin "5") (pinfunction "+IN_5") (pintype "input"))
      (node (ref "IC9") (pin "10") (pinfunction "+IN_10") (pintype "input"))
      (node (ref "IC9") (pin "11") (pinfunction "V-_11") (pintype "power_in"))
      (node (ref "IC9") (pin "12") (pinfunction "+IN_12") (pintype "input"))
      (node (ref "IC9") (pin "3") (pinfunction "+IN_3") (pintype "input"))
      (node (ref "IC9") (pin "5") (pinfunction "+IN_5") (pintype "input"))
      (node (ref "J1") (pin "P1") (pinfunction "1_P1") (pintype "passive"))
      (node (ref "J10") (pin "P1") (pinfunction "1_P1") (pintype "passive"))
      (node (ref "J11") (pin "P1") (pinfunction "1_P1") (pintype "passive"))
      (node (ref "J12") (pin "P1") (pinfunction "1_P1") (pintype "passive"))
      (node (ref "J13") (pin "P1") (pinfunction "1_P1") (pintype "passive"))
      (node (ref "J2") (pin "P1") (pinfunction "1_P1") (pintype "passive"))
      (node (ref "J3") (pin "P1") (pinfunction "1_P1") (pintype "passive"))
      (node (ref "J4") (pin "P1") (pinfunction "1_P1") (pintype "passive"))
      (node (ref "J4") (pin "P2") (pinfunction "2_P2") (pintype "passive"))
      (node (ref "J5") (pin "P1") (pinfunction "1_P1") (pintype "passive"))
      (node (ref "J5") (pin "P2") (pinfunction "2_P2") (pintype "passive"))
      (node (ref "J6") (pin "P1") (pinfunction "1_P1") (pintype "passive"))
      (node (ref "J7") (pin "P1") (pinfunction "1_P1") (pintype "passive"))
      (node (ref "J8") (pin "P1") (pinfunction "1_P1") (pintype "passive"))
      (node (ref "J9") (pin "P1") (pinfunction "1_P1") (pintype "passive"))
      (node (ref "J9") (pin "P2") (pinfunction "2_P2") (pintype "passive"))
      (node (ref "JP1") (pin "3") (pinfunction "3_3") (pintype "passive"))
      (node (ref "JP1") (pin "4") (pinfunction "4_4") (pintype "passive"))
      (node (ref "JP1") (pin "5") (pinfunction "5_5") (pintype "passive"))
      (node (ref "JP1") (pin "6") (pinfunction "6_6") (pintype "passive"))
      (node (ref "JP1") (pin "7") (pinfunction "7_7") (pintype "passive"))
      (node (ref "JP1") (pin "8") (pinfunction "8_8") (pintype "passive"))
      (node (ref "JP2") (pin "3") (pinfunction "3_3") (pintype "passive"))
      (node (ref "JP2") (pin "5") (pinfunction "5_5") (pintype "passive"))
      (node (ref "JP2") (pin "9") (pinfunction "9_9") (pintype "passive"))
      (node (ref "JP3") (pin "1") (pinfunction "1_1") (pintype "passive"))
      (node (ref "LED1") (pin "2") (pinfunction "C_2") (pintype "bidirectional"))
      (node (ref "LED2") (pin "2") (pinfunction "C_2") (pintype "bidirectional"))
      (node (ref "LED3") (pin "2") (pinfunction "C_2") (pintype "bidirectional"))
      (node (ref "Q2") (pin "E") (pinfunction "E_E") (pintype "passive"))
      (node (ref "Q3") (pin "E") (pinfunction "E_E") (pintype "passive"))
      (node (ref "Q4") (pin "E") (pinfunction "E_E") (pintype "passive"))
      (node (ref "Q5") (pin "E") (pinfunction "E_E") (pintype "passive"))
      (node (ref "Q6") (pin "E") (pinfunction "E_E") (pintype "passive"))
      (node (ref "R1") (pin "1") (pinfunction "1_1") (pintype "passive"))
      (node (ref "R17") (pin "P$1") (pinfunction "E_P$1") (pintype "passive"))
      (node (ref "R18") (pin "P$1") (pinfunction "E_P$1") (pintype "passive"))
      (node (ref "R19") (pin "P$1") (pinfunction "E_P$1") (pintype "passive"))
      (node (ref "R26") (pin "1") (pinfunction "1_1") (pintype "passive"))
      (node (ref "R50") (pin "1") (pinfunction "1_1") (pintype "passive"))
      (node (ref "R52") (pin "1") (pinfunction "1_1") (pintype "passive"))
      (node (ref "R6") (pin "P$3") (pinfunction "A_P$3") (pintype "passive"))
      (node (ref "R8") (pin "1") (pinfunction "1_1") (pintype "passive"))
      (node (ref "SW2") (pin "A") (pinfunction "P_A") (pintype "passive"))
      (node (ref "SW2") (pin "A'") (pinfunction "P1_A'") (pintype "passive"))
      (node (ref "SW3") (pin "B1") (pinfunction "P_B1") (pintype "passive"))
      (node (ref "SW3") (pin "B2") (pinfunction "P1_B2") (pintype "passive"))
      (node (ref "SW4") (pin "B1") (pinfunction "P_B1") (pintype "passive"))
      (node (ref "SW4") (pin "B2") (pinfunction "P1_B2") (pintype "passive"))
      (node (ref "UC1") (pin "20") (pinfunction "PB2/BOOT1_20") (pintype "bidirectional"))
      (node (ref "UC1") (pin "23") (pinfunction "VSS_1_23") (pintype "power_in"))
      (node (ref "UC1") (pin "35") (pinfunction "VSS_2_35") (pintype "power_in"))
      (node (ref "UC1") (pin "47") (pinfunction "VSS_3_47") (pintype "power_in"))
      (node (ref "UC1") (pin "8") (pinfunction "VSS_A_8") (pintype "power_in"))
    )
    (net (code "19") (name "JTCK") (class "Default")
      (node (ref "JP2") (pin "4") (pinfunction "4_4") (pintype "passive"))
      (node (ref "UC1") (pin "37") (pinfunction "PA14/JTCK/SWCLK_37") (pintype "bidirectional"))
    )
    (net (code "20") (name "JTDI") (class "Default")
      (node (ref "JP2") (pin "8") (pinfunction "8_8") (pintype "passive"))
      (node (ref "UC1") (pin "38") (pinfunction "PA15/JTDI_38") (pintype "bidirectional"))
    )
    (net (code "21") (name "JTDO") (class "Default")
      (node (ref "JP2") (pin "6") (pinfunction "6_6") (pintype "passive"))
      (node (ref "UC1") (pin "39") (pinfunction "PB3/JTDO_39") (pintype "bidirectional"))
    )
    (net (code "22") (name "JTMS") (class "Default")
      (node (ref "JP2") (pin "2") (pinfunction "2_2") (pintype "passive"))
      (node (ref "UC1") (pin "34") (pinfunction "PA13/JTMS/SWDIO_34") (pintype "bidirectional"))
    )
    (net (code "23") (name "LEVEL_ADC") (class "Default")
      (node (ref "C34") (pin "2") (pinfunction "2_2") (pintype "passive"))
      (node (ref "IC9") (pin "7") (pinfunction "OUT_7") (pintype "output"))
      (node (ref "R45") (pin "1") (pinfunction "1_1") (pintype "passive"))
      (node (ref "UC1") (pin "16") (pinfunction "PA6/SPI1_MISO/ADC12_IN6/TIM3_CH1_16") (pintype "bidirectional"))
    )
    (net (code "24") (name "Net-(C19-Pad1)") (class "Default")
      (node (ref "C19") (pin "1") (pinfunction "1_1") (pintype "passive"))
      (node (ref "R13") (pin "1") (pinfunction "1_1") (pintype "passive"))
      (node (ref "R15") (pin "2") (pinfunction "2_2") (pintype "passive"))
    )
    (net (code "25") (name "Net-(C21-Pad1)") (class "Default")
      (node (ref "C21") (pin "1") (pinfunction "1_1") (pintype "passive"))
      (node (ref "R14") (pin "1") (pinfunction "1_1") (pintype "passive"))
      (node (ref "R16") (pin "2") (pinfunction "2_2") (pintype "passive"))
    )
    (net (code "26") (name "Net-(D1-PadA)") (class "Default")
      (node (ref "D1") (pin "A") (pinfunction "A_A") (pintype "passive"))
      (node (ref "JP1") (pin "1") (pinfunction "1_1") (pintype "passive"))
      (node (ref "JP1") (pin "2") (pinfunction "2_2") (pintype "passive"))
    )
    (net (code "27") (name "Net-(D2-PadC)") (class "Default")
      (node (ref "D2") (pin "C") (pinfunction "C_C") (pintype "passive"))
      (node (ref "JP1") (pin "10") (pinfunction "10_10") (pintype "passive"))
      (node (ref "JP1") (pin "9") (pinfunction "9_9") (pintype "passive"))
    )
    (net (code "28") (name "Net-(IC5A--IN)") (class "Default")
      (node (ref "IC5") (pin "2") (pinfunction "-IN_2") (pintype "input"))
      (node (ref "R20") (pin "1") (pinfunction "1_1") (pintype "passive"))
      (node (ref "R21") (pin "1") (pinfunction "1_1") (pintype "passive"))
      (node (ref "R23") (pin "2") (pinfunction "2_2") (pintype "passive"))
    )
    (net (code "29") (name "Net-(IC5A-OUT)") (class "Default")
      (node (ref "IC5") (pin "1") (pinfunction "OUT_1") (pintype "output"))
      (node (ref "R22") (pin "2") (pinfunction "2_2") (pintype "passive"))
      (node (ref "R23") (pin "1") (pinfunction "1_1") (pintype "passive"))
    )
    (net (code "30") (name "Net-(IC5B-+IN)") (class "Default")
      (node (ref "C22") (pin "1") (pinfunction "1_1") (pintype "passive"))
      (node (ref "IC5") (pin "5") (pinfunction "+IN_5") (pintype "input"))
      (node (ref "R15") (pin "1") (pinfunction "1_1") (pintype "passive"))
    )
    (net (code "31") (name "Net-(IC5B--IN)") (class "Default")
      (node (ref "C19") (pin "2") (pinfunction "2_2") (pintype "passive"))
      (node (ref "IC5") (pin "6") (pinfunction "-IN_6") (pintype "input"))
      (node (ref "IC5") (pin "7") (pinfunction "OUT_7") (pintype "output"))
      (node (ref "R20") (pin "2") (pinfunction "2_2") (pintype "passive"))
    )
    (net (code "32") (name "Net-(IC6A-+IN)") (class "Default")
      (node (ref "C21") (pin "2") (pinfunction "2_2") (pintype "passive"))
      (node (ref "IC6") (pin "3") (pinfunction "+IN_3") (pintype "input"))
      (node (ref "IC6") (pin "6") (pinfunction "-IN_6") (pintype "input"))
      (node (ref "IC6") (pin "7") (pinfunction "OUT_7") (pintype "output"))
    )
    (net (code "33") (name "Net-(IC6A--IN)") (class "Default")
      (node (ref "IC6") (pin "2") (pinfunction "-IN_2") (pintype "input"))
      (node (ref "R25") (pin "2") (pinfunction "2_2") (pintype "passive"))
      (node (ref "R26") (pin "2") (pinfunction "2_2") (pintype "passive"))
    )
    (net (code "34") (name "Net-(IC6A-OUT)") (class "Default")
      (node (ref "IC6") (pin "1") (pinfunction "OUT_1") (pintype "output"))
      (node (ref "R24") (pin "2") (pinfunction "2_2") (pintype "passive"))
      (node (ref "R25") (pin "1") (pinfunction "1_1") (pintype "passive"))
    )
    (net (code "35") (name "Net-(IC6B-+IN)") (class "Default")
      (node (ref "C23") (pin "1") (pinfunction "1_1") (pintype "passive"))
      (node (ref "IC6") (pin "5") (pinfunction "+IN_5") (pintype "input"))
      (node (ref "R16") (pin "1") (pinfunction "1_1") (pintype "passive"))
    )
    (net (code "36") (name "Net-(IC8A--IN)") (class "Default")
      (node (ref "C31") (pin "1") (pinfunction "1_1") (pintype "passive"))
      (node (ref "IC8") (pin "2") (pinfunction "-IN_2") (pintype "input"))
      (node (ref "R37") (pin "2") (pinfunction "2_2") (pintype "passive"))
      (node (ref "R38") (pin "1") (pinfunction "1_1") (pintype "passive"))
      (node (ref "R39") (pin "1") (pinfunction "1_1") (pintype "passive"))
    )
    (net (code "37") (name "Net-(IC8B--IN)") (class "Default")
      (node (ref "C27") (pin "1") (pinfunction "1_1") (pintype "passive"))
      (node (ref "IC8") (pin "6") (pinfunction "-IN_6") (pintype "input"))
      (node (ref "R34") (pin "2") (pinfunction "2_2") (pintype "passive"))
      (node (ref "R35") (pin "1") (pinfunction "1_1") (pintype "passive"))
      (node (ref "R36") (pin "1") (pinfunction "1_1") (pintype "passive"))
    )
    (net (code "38") (name "Net-(IC9A--IN)") (class "Default")
      (node (ref "C32") (pin "1") (pinfunction "1_1") (pintype "passive"))
      (node (ref "IC9") (pin "2") (pinfunction "-IN_2") (pintype "input"))
      (node (ref "R40") (pin "2") (pinfunction "2_2") (pintype "passive"))
      (node (ref "R41") (pin "1") (pinfunction "1_1") (pintype "passive"))
      (node (ref "R42") (pin "1") (pinfunction "1_1") (pintype "passive"))
    )
    (net (code "39") (name "Net-(IC9B--IN)") (class "Default")
      (node (ref "C34") (pin "1") (pinfunction "1_1") (pintype "passive"))
      (node (ref "IC9") (pin "6") (pinfunction "-IN_6") (pintype "input"))
      (node (ref "R43") (pin "1") (pinfunction "1_1") (pintype "passive"))
      (node (ref "R44") (pin "1") (pinfunction "1_1") (pintype "passive"))
      (node (ref "R45") (pin "2") (pinfunction "2_2") (pintype "passive"))
    )
    (net (code "40") (name "Net-(IC9C--IN)") (class "Default")
      (node (ref "C28") (pin "1") (pinfunction "1_1") (pintype "passive"))
      (node (ref "IC9") (pin "9") (pinfunction "-IN_9") (pintype "input"))
      (node (ref "R31") (pin "1") (pinfunction "1_1") (pintype "passive"))
      (node (ref "R32") (pin "1") (pinfunction "1_1") (pintype "passive"))
      (node (ref "R33") (pin "2") (pinfunction "2_2") (pintype "passive"))
    )
    (net (code "41") (name "Net-(IC9D--IN)") (class "Default")
      (node (ref "C29") (pin "1") (pinfunction "1_1") (pintype "passive"))
      (node (ref "IC9") (pin "13") (pinfunction "-IN_13") (pintype "input"))
      (node (ref "R28") (pin "2") (pinfunction "2_2") (pintype "passive"))
      (node (ref "R29") (pin "1") (pinfunction "1_1") (pintype "passive"))
      (node (ref "R30") (pin "1") (pinfunction "1_1") (pintype "passive"))
    )
    (net (code "42") (name "Net-(J1-3)") (class "Default")
      (node (ref "J1") (pin "P3") (pinfunction "3_P3") (pintype "passive"))
      (node (ref "R42") (pin "2") (pinfunction "2_2") (pintype "passive"))
    )
    (net (code "43") (name "Net-(J2-3)") (class "Default")
      (node (ref "J2") (pin "P3") (pinfunction "3_P3") (pintype "passive"))
      (node (ref "R29") (pin "2") (pinfunction "2_2") (pintype "passive"))
    )
    (net (code "44") (name "Net-(J3-3)") (class "Default")
      (node (ref "J3") (pin "P3") (pinfunction "3_P3") (pintype "passive"))
      (node (ref "R32") (pin "2") (pinfunction "2_2") (pintype "passive"))
    )
    (net (code "45") (name "Net-(J4-3)") (class "Default")
      (node (ref "J4") (pin "P3") (pinfunction "3_P3") (pintype "passive"))
      (node (ref "R55") (pin "1") (pinfunction "1_1") (pintype "passive"))
    )
    (net (code "46") (name "Net-(J5-3)") (class "Default")
      (node (ref "J5") (pin "P3") (pinfunction "3_P3") (pintype "passive"))
      (node (ref "R56") (pin "1") (pinfunction "1_1") (pintype "passive"))
    )
    (net (code "47") (name "Net-(J6-3)") (class "Default")
      (node (ref "J6") (pin "P3") (pinfunction "3_P3") (pintype "passive"))
      (node (ref "R39") (pin "2") (pinfunction "2_2") (pintype "passive"))
    )
    (net (code "48") (name "Net-(J7-2)") (class "Default")
      (node (ref "J7") (pin "P2") (pinfunction "2_P2") (pintype "passive"))
      (node (ref "R46") (pin "1") (pinfunction "1_1") (pintype "passive"))
    )
    (net (code "49") (name "Net-(J7-3)") (class "Default")
      (node (ref "J7") (pin "P3") (pinfunction "3_P3") (pintype "passive"))
      (node (ref "R36") (pin "2") (pinfunction "2_2") (pintype "passive"))
    )
    (net (code "50") (name "Net-(J8-2)") (class "Default")
      (node (ref "J8") (pin "P2") (pinfunction "2_P2") (pintype "passive"))
      (node (ref "R60") (pin "2") (pinfunction "2_2") (pintype "passive"))
    )
    (net (code "51") (name "Net-(J8-3)") (class "Default")
      (node (ref "J8") (pin "P3") (pinfunction "3_P3") (pintype "passive"))
      (node (ref "R44") (pin "2") (pinfunction "2_2") (pintype "passive"))
    )
    (net (code "52") (name "Net-(J9-3)") (class "Default")
      (node (ref "J9") (pin "P3") (pinfunction "3_P3") (pintype "passive"))
      (node (ref "R54") (pin "1") (pinfunction "1_1") (pintype "passive"))
    )
    (net (code "53") (name "Net-(J10-3)") (class "Default")
      (node (ref "J10") (pin "P3") (pinfunction "3_P3") (pintype "passive"))
      (node (ref "Q5") (pin "C") (pinfunction "C_C") (pintype "passive"))
      (node (ref "R50") (pin "2") (pinfunction "2_2") (pintype "passive"))
      (node (ref "R51") (pin "1") (pinfunction "1_1") (pintype "passive"))
    )
    (net (code "54") (name "Net-(J11-3)") (class "Default")
      (node (ref "J11") (pin "P3") (pinfunction "3_P3") (pintype "passive"))
      (node (ref "Q6") (pin "C") (pinfunction "C_C") (pintype "passive"))
      (node (ref "R52") (pin "2") (pinfunction "2_2") (pintype "passive"))
      (node (ref "R53") (pin "1") (pinfunction "1_1") (pintype "passive"))
    )
    (net (code "55") (name "Net-(J12-3)") (class "Default")
      (node (ref "J12") (pin "P3") (pinfunction "3_P3") (pintype "passive"))
      (node (ref "R24") (pin "1") (pinfunction "1_1") (pintype "passive"))
    )
    (net (code "56") (name "Net-(J13-3)") (class "Default")
      (node (ref "J13") (pin "P3") (pinfunction "3_P3") (pintype "passive"))
      (node (ref "R22") (pin "1") (pinfunction "1_1") (pintype "passive"))
    )
    (net (code "57") (name "Net-(LED1-GRN)") (class "Default")
      (node (ref "LED1") (pin "1") (pinfunction "GRN_1") (pintype "bidirectional"))
      (node (ref "R2") (pin "2") (pinfunction "2_2") (pintype "passive"))
    )
    (net (code "58") (name "Net-(LED1-RED)") (class "Default")
      (node (ref "LED1") (pin "3") (pinfunction "RED_3") (pintype "bidirectional"))
      (node (ref "R3") (pin "2") (pinfunction "2_2") (pintype "passive"))
    )
    (net (code "59") (name "Net-(LED2-GRN)") (class "Default")
      (node (ref "LED2") (pin "1") (pinfunction "GRN_1") (pintype "bidirectional"))
      (node (ref "R4") (pin "2") (pinfunction "2_2") (pintype "passive"))
    )
    (net (code "60") (name "Net-(LED2-RED)") (class "Default")
      (node (ref "LED2") (pin "3") (pinfunction "RED_3") (pintype "bidirectional"))
      (node (ref "R7") (pin "2") (pinfunction "2_2") (pintype "passive"))
    )
    (net (code "61") (name "Net-(LED3-GRN)") (class "Default")
      (node (ref "LED3") (pin "1") (pinfunction "GRN_1") (pintype "bidirectional"))
      (node (ref "R9") (pin "2") (pinfunction "2_2") (pintype "passive"))
    )
    (net (code "62") (name "Net-(LED3-RED)") (class "Default")
      (node (ref "LED3") (pin "3") (pinfunction "RED_3") (pintype "bidirectional"))
      (node (ref "R10") (pin "2") (pinfunction "2_2") (pintype "passive"))
    )
    (net (code "63") (name "Net-(Q2-PadB)") (class "Default")
      (node (ref "Q2") (pin "B") (pinfunction "B_B") (pintype "passive"))
      (node (ref "R55") (pin "2") (pinfunction "2_2") (pintype "passive"))
    )
    (net (code "64") (name "Net-(Q3-PadB)") (class "Default")
      (node (ref "Q3") (pin "B") (pinfunction "B_B") (pintype "passive"))
      (node (ref "R54") (pin "2") (pinfunction "2_2") (pintype "passive"))
    )
    (net (code "65") (name "Net-(Q4-PadB)") (class "Default")
      (node (ref "Q4") (pin "B") (pinfunction "B_B") (pintype "passive"))
      (node (ref "R56") (pin "2") (pinfunction "2_2") (pintype "passive"))
    )
    (net (code "66") (name "Net-(Q5-PadB)") (class "Default")
      (node (ref "Q5") (pin "B") (pinfunction "B_B") (pintype "passive"))
      (node (ref "R57") (pin "2") (pinfunction "2_2") (pintype "passive"))
    )
    (net (code "67") (name "Net-(Q6-PadB)") (class "Default")
      (node (ref "Q6") (pin "B") (pinfunction "B_B") (pintype "passive"))
      (node (ref "R58") (pin "2") (pinfunction "2_2") (pintype "passive"))
    )
    (net (code "68") (name "Net-(R5-E)") (class "Default")
      (node (ref "R5") (pin "P$1") (pinfunction "E_P$1") (pintype "passive"))
      (node (ref "R8") (pin "2") (pinfunction "2_2") (pintype "passive"))
    )
    (net (code "69") (name "Net-(R5-S)") (class "Default")
      (node (ref "R38") (pin "2") (pinfunction "2_2") (pintype "passive"))
      (node (ref "R5") (pin "P$2") (pinfunction "S_P$2") (pintype "passive"))
    )
    (net (code "70") (name "Net-(R17-S)") (class "Default")
      (node (ref "R17") (pin "P$2") (pinfunction "S_P$2") (pintype "passive"))
      (node (ref "R41") (pin "2") (pinfunction "2_2") (pintype "passive"))
    )
    (net (code "71") (name "Net-(R18-S)") (class "Default")
      (node (ref "R18") (pin "P$2") (pinfunction "S_P$2") (pintype "passive"))
      (node (ref "R30") (pin "2") (pinfunction "2_2") (pintype "passive"))
    )
    (net (code "72") (name "Net-(R19-S)") (class "Default")
      (node (ref "R19") (pin "P$2") (pinfunction "S_P$2") (pintype "passive"))
      (node (ref "R31") (pin "2") (pinfunction "2_2") (pintype "passive"))
    )
    (net (code "73") (name "Net-(R59-E)") (class "Default")
      (node (ref "R21") (pin "2") (pinfunction "2_2") (pintype "passive"))
      (node (ref "R59") (pin "1") (pinfunction "E_1") (pintype "passive"))
    )
    (net (code "74") (name "Net-(UC1-PB4{slash}NJTRST)") (class "Default")
      (node (ref "R2") (pin "1") (pinfunction "1_1") (pintype "passive"))
      (node (ref "UC1") (pin "40") (pinfunction "PB4/NJTRST_40") (pintype "bidirectional"))
    )
    (net (code "75") (name "Net-(UC1-PB5{slash}I2C1_SMBA)") (class "Default")
      (node (ref "R3") (pin "1") (pinfunction "1_1") (pintype "passive"))
      (node (ref "UC1") (pin "41") (pinfunction "PB5/I2C1_SMBA_41") (pintype "input"))
    )
    (net (code "76") (name "Net-(UC1-PB6{slash}I2C1_SCL{slash}TIM4_CH1)") (class "Default")
      (node (ref "R4") (pin "1") (pinfunction "1_1") (pintype "passive"))
      (node (ref "UC1") (pin "42") (pinfunction "PB6/I2C1_SCL/TIM4_CH1_42") (pintype "input"))
    )
    (net (code "77") (name "Net-(UC1-PB7{slash}I2C1_SDA{slash}TIM4_CH2)") (class "Default")
      (node (ref "R7") (pin "1") (pinfunction "1_1") (pintype "passive"))
      (node (ref "UC1") (pin "43") (pinfunction "PB7/I2C1_SDA/TIM4_CH2_43") (pintype "bidirectional"))
    )
    (net (code "78") (name "Net-(UC1-PB8{slash}TIM4_CH3)") (class "Default")
      (node (ref "R9") (pin "1") (pinfunction "1_1") (pintype "passive"))
      (node (ref "UC1") (pin "45") (pinfunction "PB8/TIM4_CH3_45") (pintype "bidirectional"))
    )
    (net (code "79") (name "Net-(UC1-PB9{slash}TIM4_CH4)") (class "Default")
      (node (ref "R10") (pin "1") (pinfunction "1_1") (pintype "passive"))
      (node (ref "UC1") (pin "46") (pinfunction "PB9/TIM4_CH4_46") (pintype "input"))
    )
    (net (code "80") (name "Net-(UC1-PD0-OSC_IN)") (class "Default")
      (node (ref "C2") (pin "2") (pinfunction "2_2") (pintype "passive"))
      (node (ref "Q1") (pin "2") (pinfunction "2_2") (pintype "passive"))
      (node (ref "UC1") (pin "5") (pinfunction "PD0-OSC_IN_5") (pintype "input"))
    )
    (net (code "81") (name "Net-(UC1-PD1-OSC_OUT)") (class "Default")
      (node (ref "C17") (pin "2") (pinfunction "2_2") (pintype "passive"))
      (node (ref "Q1") (pin "1") (pinfunction "1_1") (pintype "passive"))
      (node (ref "UC1") (pin "6") (pinfunction "PD1-OSC_OUT_6") (pintype "input"))
    )
    (net (code "82") (name "PROC_ADC") (class "Default")
      (node (ref "C28") (pin "2") (pinfunction "2_2") (pintype "passive"))
      (node (ref "IC9") (pin "8") (pinfunction "OUT_8") (pintype "output"))
      (node (ref "R33") (pin "1") (pinfunction "1_1") (pintype "passive"))
      (node (ref "UC1") (pin "17") (pinfunction "PA7/SPI1_MOSI/ADC12_IN7/TIM3_CH2_17") (pintype "bidirectional"))
    )
    (net (code "83") (name "RANGE_SW") (class "Default")
      (node (ref "SW4") (pin "A1") (pinfunction "S_A1") (pintype "passive"))
      (node (ref "SW4") (pin "A2") (pinfunction "S1_A2") (pintype "passive"))
      (node (ref "UC1") (pin "11") (pinfunction "PA1/USART2_RTS/ADC12_IN1/TIM2_CH2_11") (pintype "bidirectional"))
    )
    (net (code "84") (name "RESET") (class "Default")
      (node (ref "JP2") (pin "10") (pinfunction "10_10") (pintype "passive"))
      (node (ref "R11") (pin "1") (pinfunction "1_1") (pintype "passive"))
      (node (ref "SW2") (pin "B") (pinfunction "S_B") (pintype "passive"))
      (node (ref "SW2") (pin "B'") (pinfunction "S1_B'") (pintype "passive"))
      (node (ref "UC1") (pin "7") (pinfunction "NRST_7") (pintype "input"))
    )
    (net (code "85") (name "RX") (class "Default")
      (node (ref "JP3") (pin "4") (pinfunction "4_4") (pintype "passive"))
      (node (ref "UC1") (pin "31") (pinfunction "PA10/USART1_RX/TIM1_CH3_31") (pintype "bidirectional"))
    )
    (net (code "86") (name "SHAPE_ADC") (class "Default")
      (node (ref "C32") (pin "2") (pinfunction "2_2") (pintype "passive"))
      (node (ref "IC9") (pin "1") (pinfunction "OUT_1") (pintype "output"))
      (node (ref "R40") (pin "1") (pinfunction "1_1") (pintype "passive"))
      (node (ref "UC1") (pin "15") (pinfunction "PA5/SPI1_SCK/ADC12_IN5_15") (pintype "bidirectional"))
    )
    (net (code "87") (name "START") (class "Default")
      (node (ref "Q2") (pin "C") (pinfunction "C_C") (pintype "passive"))
      (node (ref "R47") (pin "1") (pinfunction "1_1") (pintype "passive"))
      (node (ref "UC1") (pin "22") (pinfunction "PB11/I2C2_SDA/USART3_RX_22") (pintype "input"))
    )
    (net (code "88") (name "TX") (class "Default")
      (node (ref "JP3") (pin "5") (pinfunction "5_5") (pintype "passive"))
      (node (ref "UC1") (pin "30") (pinfunction "PA9/USART1_TX/TIM1_CH2_30") (pintype "input"))
    )
    (net (code "89") (name "UNI") (class "Default")
      (node (ref "IC4") (pin "4") (pinfunction "OUTA_4") (pintype "output"))
      (node (ref "R14") (pin "2") (pinfunction "2_2") (pintype "passive"))
    )
    (net (code "90") (name "VCC") (class "Default")
      (node (ref "C18") (pin "1") (pinfunction "1_1") (pintype "passive"))
      (node (ref "C20") (pin "1") (pinfunction "1_1") (pintype "passive"))
      (node (ref "C3") (pin "+") (pinfunction "+_+") (pintype "passive"))
      (node (ref "C8") (pin "+") (pinfunction "+_+") (pintype "passive"))
      (node (ref "D1") (pin "C") (pinfunction "C_C") (pintype "passive"))
      (node (ref "IC1") (pin "3") (pinfunction "VIN_3") (pintype "input"))
      (node (ref "IC3") (pin "3") (pinfunction "VIN_3") (pintype "input"))
      (node (ref "IC5") (pin "8") (pinfunction "V+_8") (pintype "power_in"))
      (node (ref "IC6") (pin "8") (pinfunction "V+_8") (pintype "power_in"))
      (node (ref "R51") (pin "2") (pinfunction "2_2") (pintype "passive"))
      (node (ref "R53") (pin "2") (pinfunction "2_2") (pintype "passive"))
      (node (ref "R60") (pin "1") (pinfunction "1_1") (pintype "passive"))
    )
    (net (code "91") (name "VEE") (class "Default")
      (node (ref "C10") (pin "-") (pinfunction "-_-") (pintype "passive"))
      (node (ref "C24") (pin "2") (pinfunction "2_2") (pintype "passive"))
      (node (ref "C25") (pin "2") (pinfunction "2_2") (pintype "passive"))
      (node (ref "D2") (pin "A") (pinfunction "A_A") (pintype "passive"))
      (node (ref "IC5") (pin "4") (pinfunction "V-_4") (pintype "power_in"))
      (node (ref "IC6") (pin "4") (pinfunction "V-_4") (pintype "power_in"))
      (node (ref "R27") (pin "1") (pinfunction "1_1") (pintype "passive"))
    )
    (net (code "92") (name "VOCT_ADC") (class "Default")
      (node (ref "C31") (pin "2") (pinfunction "2_2") (pintype "passive"))
      (node (ref "IC8") (pin "1") (pinfunction "OUT_1") (pintype "output"))
      (node (ref "R37") (pin "1") (pinfunction "1_1") (pintype "passive"))
      (node (ref "UC1") (pin "13") (pinfunction "PA3/USART2_RX/ADC12_IN3/TIM2_CH4_13") (pintype "bidirectional"))
    )
    (net (code "93") (name "unconnected-(J1-2-PadP2)") (class "Default")
      (node (ref "J1") (pin "P2") (pinfunction "2_P2") (pintype "passive"))
    )
    (net (code "94") (name "unconnected-(J2-2-PadP2)") (class "Default")
      (node (ref "J2") (pin "P2") (pinfunction "2_P2") (pintype "passive"))
    )
    (net (code "95") (name "unconnected-(J3-2-PadP2)") (class "Default")
      (node (ref "J3") (pin "P2") (pinfunction "2_P2") (pintype "passive"))
    )
    (net (code "96") (name "unconnected-(J6-2-PadP2)") (class "Default")
      (node (ref "J6") (pin "P2") (pinfunction "2_P2") (pintype "passive"))
    )
    (net (code "97") (name "unconnected-(J10-2-PadP2)") (class "Default")
      (node (ref "J10") (pin "P2") (pinfunction "2_P2") (pintype "passive"))
    )
    (net (code "98") (name "unconnected-(J11-2-PadP2)") (class "Default")
      (node (ref "J11") (pin "P2") (pinfunction "2_P2") (pintype "passive"))
    )
    (net (code "99") (name "unconnected-(J12-2-PadP2)") (class "Default")
      (node (ref "J12") (pin "P2") (pinfunction "2_P2") (pintype "passive"))
    )
    (net (code "100") (name "unconnected-(J13-2-PadP2)") (class "Default")
      (node (ref "J13") (pin "P2") (pinfunction "2_P2") (pintype "passive"))
    )
    (net (code "101") (name "unconnected-(JP2-Pad7)") (class "Default")
      (node (ref "JP2") (pin "7") (pinfunction "7_7") (pintype "passive"))
    )
    (net (code "102") (name "unconnected-(JP3-Pad2)") (class "Default")
      (node (ref "JP3") (pin "2") (pinfunction "2_2") (pintype "passive"))
    )
    (net (code "103") (name "unconnected-(JP3-Pad3)") (class "Default")
      (node (ref "JP3") (pin "3") (pinfunction "3_3") (pintype "passive"))
    )
    (net (code "104") (name "unconnected-(JP3-Pad6)") (class "Default")
      (node (ref "JP3") (pin "6") (pinfunction "6_6") (pintype "passive"))
    )
    (net (code "105") (name "unconnected-(UC1-PA8{slash}USART1_CK{slash}TIM1_CH1{slash}MCO-Pad29)") (class "Default")
      (node (ref "UC1") (pin "29") (pinfunction "PA8/USART1_CK/TIM1_CH1/MCO_29") (pintype "bidirectional"))
    )
    (net (code "106") (name "unconnected-(UC1-PB14{slash}SPI2_MISO{slash}USART3_RTS{slash}TIM1_CH2N-Pad27)") (class "Default")
      (node (ref "UC1") (pin "27") (pinfunction "PB14/SPI2_MISO/USART3_RTS/TIM1_CH2N_27") (pintype "input"))
    )
    (net (code "107") (name "unconnected-(UC1-PC13-TAMPER-RTC-Pad2)") (class "Default")
      (node (ref "UC1") (pin "2") (pinfunction "PC13-TAMPER-RTC_2") (pintype "input"))
    )
    (net (code "108") (name "unconnected-(UC1-PC14-OSC32_IN-Pad3)") (class "Default")
      (node (ref "UC1") (pin "3") (pinfunction "PC14-OSC32_IN_3") (pintype "input"))
    )
    (net (code "109") (name "unconnected-(UC1-PC15-OSC32_OUT-Pad4)") (class "Default")
      (node (ref "UC1") (pin "4") (pinfunction "PC15-OSC32_OUT_4") (pintype "input"))
    )
  )
)
